# SmartEVSEv2_2.net
KiCad netlist of a schematic drawn in EAGLE
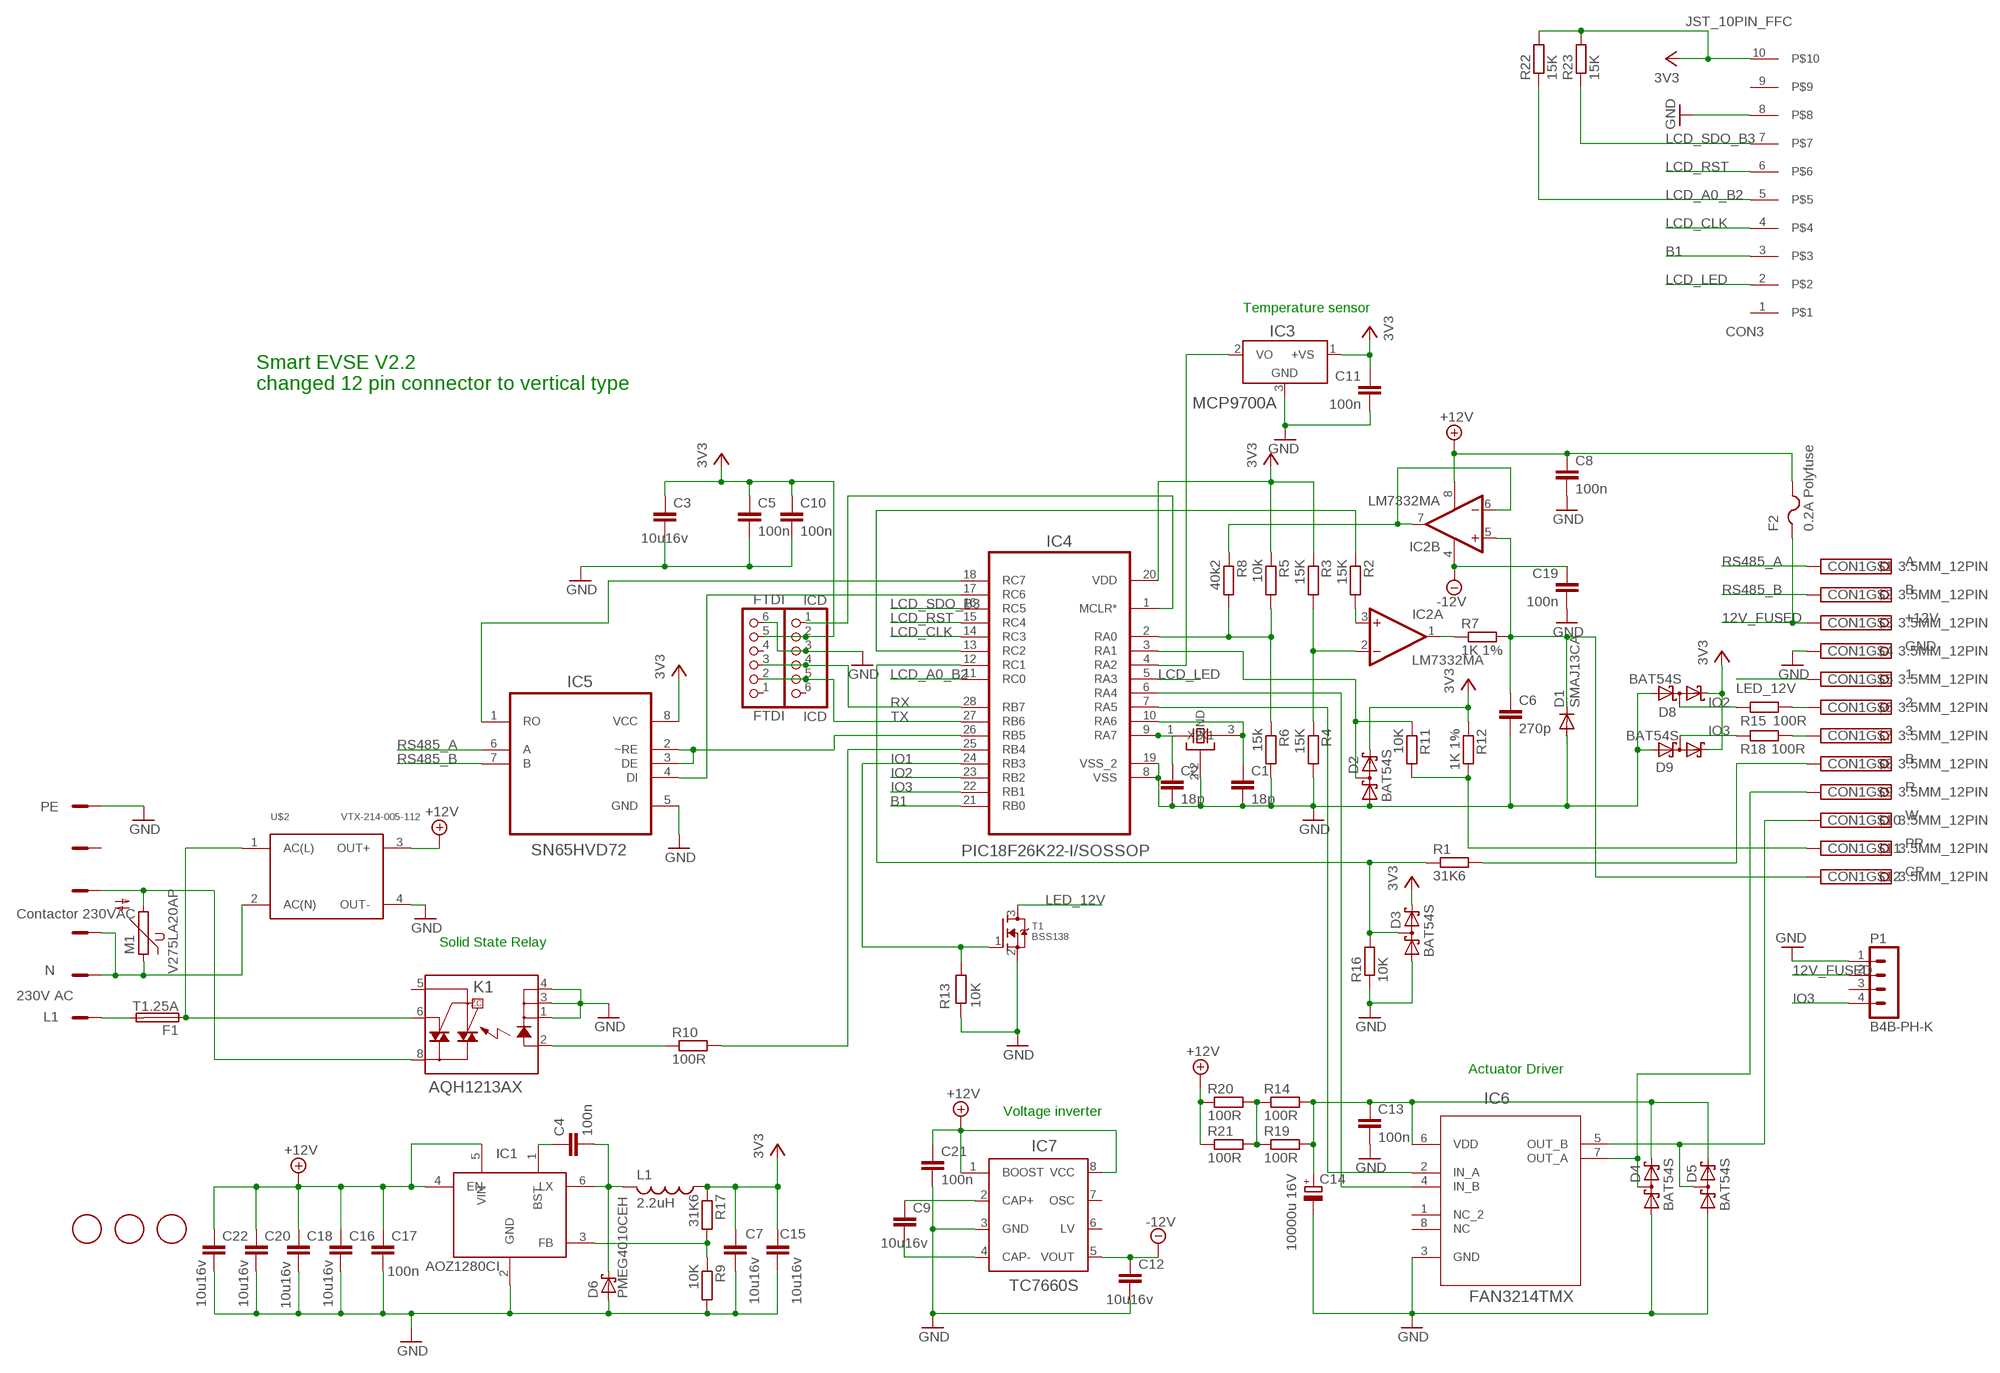
[diagram p0: schematic, sheet 1]

(export (version "E")
  (design (tool "Eeschema 10.0.6"))
  (components
    (comp (ref "C1")
      (value "18p")
      (footprint "eagle-import:C0603")
      (libsource (lib "eagle-import") (part "C-EUC0603"))
    )
    (comp (ref "C2")
      (value "18p")
      (footprint "eagle-import:C0603")
      (libsource (lib "eagle-import") (part "C-EUC0603"))
    )
    (comp (ref "C3")
      (value "10u16v")
      (footprint "eagle-import:C0805")
      (libsource (lib "eagle-import") (part "C-EUC0805"))
    )
    (comp (ref "C4")
      (value "100n")
      (footprint "eagle-import:C0603")
      (libsource (lib "eagle-import") (part "C-EUC0603"))
    )
    (comp (ref "C5")
      (value "100n")
      (footprint "eagle-import:C0603")
      (libsource (lib "eagle-import") (part "C-EUC0603"))
    )
    (comp (ref "C6")
      (value "270p")
      (footprint "eagle-import:C0805")
      (libsource (lib "eagle-import") (part "C-EUC0805"))
    )
    (comp (ref "C7")
      (value "10u16v")
      (footprint "eagle-import:C0805")
      (libsource (lib "eagle-import") (part "C-EUC0805"))
    )
    (comp (ref "C8")
      (value "100n")
      (footprint "eagle-import:C0603")
      (libsource (lib "eagle-import") (part "C-EUC0603"))
    )
    (comp (ref "C9")
      (value "10u16v")
      (footprint "eagle-import:C0805")
      (libsource (lib "eagle-import") (part "C-EUC0805"))
    )
    (comp (ref "C10")
      (value "100n")
      (footprint "eagle-import:C0603")
      (libsource (lib "eagle-import") (part "C-EUC0603"))
    )
    (comp (ref "C11")
      (value "100n")
      (footprint "eagle-import:C0603")
      (libsource (lib "eagle-import") (part "C-EUC0603"))
    )
    (comp (ref "C12")
      (value "10u16v")
      (footprint "eagle-import:C0805")
      (libsource (lib "eagle-import") (part "C-EUC0805"))
    )
    (comp (ref "C13")
      (value "100n")
      (footprint "eagle-import:C0603")
      (libsource (lib "eagle-import") (part "C-EUC0603"))
    )
    (comp (ref "C14")
      (value "10000u 16V")
      (footprint "eagle-import:EB22,5D")
      (libsource (lib "eagle-import") (part "CPOL-EUE10-22.5"))
    )
    (comp (ref "C15")
      (value "10u16v")
      (footprint "eagle-import:C0805")
      (libsource (lib "eagle-import") (part "C-EUC0805"))
    )
    (comp (ref "C16")
      (value "10u16v")
      (footprint "eagle-import:C0805")
      (libsource (lib "eagle-import") (part "C-EUC0805"))
    )
    (comp (ref "C17")
      (value "100n")
      (footprint "eagle-import:C0603")
      (libsource (lib "eagle-import") (part "C-EUC0603"))
    )
    (comp (ref "C18")
      (value "10u16v")
      (footprint "eagle-import:C0805")
      (libsource (lib "eagle-import") (part "C-EUC0805"))
    )
    (comp (ref "C19")
      (value "100n")
      (footprint "eagle-import:C0603")
      (libsource (lib "eagle-import") (part "C-EUC0603"))
    )
    (comp (ref "C20")
      (value "10u16v")
      (footprint "eagle-import:C0805")
      (libsource (lib "eagle-import") (part "C-EUC0805"))
    )
    (comp (ref "C21")
      (value "100n")
      (footprint "eagle-import:C0603")
      (libsource (lib "eagle-import") (part "C-EUC0603"))
    )
    (comp (ref "C22")
      (value "10u16v")
      (footprint "eagle-import:C0805")
      (libsource (lib "eagle-import") (part "C-EUC0805"))
    )
    (comp (ref "CON1")
      (value "3.5MM_12PIN")
      (footprint "eagle-import:12PIN")
      (libsource (lib "eagle-import") (part "3.5MM_12PIN"))
    )
    (comp (ref "CON2")
      (value "DG128-7.5")
      (footprint "eagle-import:P_AST027-06")
      (libsource (lib "eagle-import") (part "AST027-06"))
    )
    (comp (ref "CON3")
      (value "JST_10PIN_FFC")
      (footprint "eagle-import:JST_10PIN_FFC")
      (libsource (lib "eagle-import") (part "JST_10PIN_FFC"))
    )
    (comp (ref "D1")
      (value "SMAJ13CA")
      (footprint "eagle-import:DO214AC")
      (libsource (lib "eagle-import") (part "DIODE-DO214AC"))
    )
    (comp (ref "D2")
      (value "BAT54S")
      (footprint "eagle-import:SOT23")
      (libsource (lib "eagle-import") (part "BAT54S"))
    )
    (comp (ref "D3")
      (value "BAT54S")
      (footprint "eagle-import:SOT23")
      (libsource (lib "eagle-import") (part "BAT54S"))
    )
    (comp (ref "D4")
      (value "BAT54S")
      (footprint "eagle-import:SOT23")
      (libsource (lib "eagle-import") (part "BAT54S"))
    )
    (comp (ref "D5")
      (value "BAT54S")
      (footprint "eagle-import:SOT23")
      (libsource (lib "eagle-import") (part "BAT54S"))
    )
    (comp (ref "D6")
      (value "PMEG4010CEH")
      (footprint "eagle-import:SOD-123FL")
      (libsource (lib "eagle-import") (part "PMEG4010CEH"))
    )
    (comp (ref "D8")
      (value "BAT54S")
      (footprint "eagle-import:SOT23")
      (libsource (lib "eagle-import") (part "BAT54S"))
    )
    (comp (ref "D9")
      (value "BAT54S")
      (footprint "eagle-import:SOT23")
      (libsource (lib "eagle-import") (part "BAT54S"))
    )
    (comp (ref "F1")
      (value "T1.25A")
      (footprint "eagle-import:TE5")
      (libsource (lib "eagle-import") (part "FUSETE5"))
    )
    (comp (ref "F2")
      (value "0.2A Polyfuse")
      (footprint "eagle-import:R1210")
      (libsource (lib "eagle-import") (part "PTCFUSE-1210"))
    )
    (comp (ref "FTDI")
      (value "FTDI")
      (footprint "eagle-import:1X06-BIGLOCK")
      (libsource (lib "eagle-import") (part "PINHD-1X6LOCK"))
    )
    (comp (ref "IC1")
      (value "AOZ1280CI")
      (footprint "eagle-import:SOT23-6")
      (libsource (lib "eagle-import") (part "AOZ1280CISOT23"))
    )
    (comp (ref "IC2")
      (value "LM7332MA")
      (footprint "eagle-import:SO08")
      (libsource (lib "eagle-import") (part "1458DLM"))
    )
    (comp (ref "IC3")
      (value "MCP9700A")
      (footprint "eagle-import:SOT23")
      (libsource (lib "eagle-import") (part "LM50"))
    )
    (comp (ref "IC4")
      (value "PIC18F26K22-I/SOSSOP")
      (footprint "eagle-import:SOP65P780X200-28N")
      (libsource (lib "eagle-import") (part "PIC18F25K22-I/SOSSOP"))
    )
    (comp (ref "IC5")
      (value "SN65HVD72")
      (footprint "eagle-import:SOIC127P600X175-8N")
      (fields (field (name "MPN") "MAX487ECSA+"))
      (libsource (lib "eagle-import") (part "MAX487ECSA+"))
    )
    (comp (ref "IC6")
      (value "FAN3214TMX")
      (footprint "eagle-import:SOIC127P600X175-8N")
      (fields (field (name "MPN") "TC4424AVOA"))
      (libsource (lib "eagle-import") (part "TC4424AVOA"))
    )
    (comp (ref "IC7")
      (value "TC7660S")
      (footprint "eagle-import:SO08")
      (libsource (lib "eagle-import") (part "TL7660"))
    )
    (comp (ref "ICD")
      (value "ICD")
      (footprint "eagle-import:1X06")
      (libsource (lib "eagle-import") (part "pinhead_PINHD-1X6"))
    )
    (comp (ref "K1")
      (value "AQH1213AX")
      (footprint "eagle-import:DIL07SMD")
      (libsource (lib "eagle-import") (part "AQH213A"))
    )
    (comp (ref "L1")
      (value "2.2uH")
      (footprint "eagle-import:MCSD43")
      (libsource (lib "eagle-import") (part "MCSD43"))
    )
    (comp (ref "M1")
      (value "V275LA20AP")
      (footprint "eagle-import:S14K40")
      (libsource (lib "eagle-import") (part "S14K40"))
    )
    (comp (ref "P1")
      (value "B4B-PH-K")
      (footprint "eagle-import:B4B-PH-K")
      (libsource (lib "eagle-import") (part "B4B-PH-K"))
    )
    (comp (ref "Q1")
      (value "CTS_32X25_SMD")
      (footprint "eagle-import:CTS_32X25")
      (libsource (lib "eagle-import") (part "CTS_32X25_SMD"))
    )
    (comp (ref "R1")
      (value "31K6")
      (footprint "eagle-import:R0603")
      (libsource (lib "eagle-import") (part "R-EU_R0603"))
    )
    (comp (ref "R2")
      (value "15K")
      (footprint "eagle-import:R0603")
      (libsource (lib "eagle-import") (part "R-EU_R0603"))
    )
    (comp (ref "R3")
      (value "15K")
      (footprint "eagle-import:R0603")
      (libsource (lib "eagle-import") (part "R-EU_R0603"))
    )
    (comp (ref "R4")
      (value "15K")
      (footprint "eagle-import:R0603")
      (libsource (lib "eagle-import") (part "R-EU_R0603"))
    )
    (comp (ref "R5")
      (value "10k")
      (footprint "eagle-import:R0603")
      (libsource (lib "eagle-import") (part "R-EU_R0603"))
    )
    (comp (ref "R6")
      (value "15k")
      (footprint "eagle-import:R0603")
      (libsource (lib "eagle-import") (part "R-EU_R0603"))
    )
    (comp (ref "R7")
      (value "1K 1%")
      (footprint "eagle-import:R0603")
      (libsource (lib "eagle-import") (part "R-EU_R0603"))
    )
    (comp (ref "R8")
      (value "40k2")
      (footprint "eagle-import:R0603")
      (libsource (lib "eagle-import") (part "R-EU_R0603"))
    )
    (comp (ref "R9")
      (value "10K")
      (footprint "eagle-import:R0603")
      (libsource (lib "eagle-import") (part "R-EU_R0603"))
    )
    (comp (ref "R10")
      (value "100R")
      (footprint "eagle-import:R0603")
      (libsource (lib "eagle-import") (part "R-EU_R0603"))
    )
    (comp (ref "R11")
      (value "10K")
      (footprint "eagle-import:R0603")
      (libsource (lib "eagle-import") (part "R-EU_R0603"))
    )
    (comp (ref "R12")
      (value "1K 1%")
      (footprint "eagle-import:R0603")
      (libsource (lib "eagle-import") (part "R-EU_R0603"))
    )
    (comp (ref "R13")
      (value "10K")
      (footprint "eagle-import:R0603")
      (libsource (lib "eagle-import") (part "R-EU_R0603"))
    )
    (comp (ref "R14")
      (value "100R")
      (footprint "eagle-import:R0603")
      (libsource (lib "eagle-import") (part "R-EU_R0603"))
    )
    (comp (ref "R15")
      (value "100R")
      (footprint "eagle-import:R0603")
      (libsource (lib "eagle-import") (part "R-EU_R0603"))
    )
    (comp (ref "R16")
      (value "10K")
      (footprint "eagle-import:R0603")
      (libsource (lib "eagle-import") (part "R-EU_R0603"))
    )
    (comp (ref "R17")
      (value "31K6")
      (footprint "eagle-import:R0603")
      (libsource (lib "eagle-import") (part "R-EU_R0603"))
    )
    (comp (ref "R18")
      (value "100R")
      (footprint "eagle-import:R0603")
      (libsource (lib "eagle-import") (part "R-EU_R0603"))
    )
    (comp (ref "R19")
      (value "100R")
      (footprint "eagle-import:R0603")
      (libsource (lib "eagle-import") (part "R-EU_R0603"))
    )
    (comp (ref "R20")
      (value "100R")
      (footprint "eagle-import:R0603")
      (libsource (lib "eagle-import") (part "R-EU_R0603"))
    )
    (comp (ref "R21")
      (value "100R")
      (footprint "eagle-import:R0603")
      (libsource (lib "eagle-import") (part "R-EU_R0603"))
    )
    (comp (ref "R22")
      (value "15K")
      (footprint "eagle-import:R0603")
      (libsource (lib "eagle-import") (part "R-EU_R0603"))
    )
    (comp (ref "R23")
      (value "15K")
      (footprint "eagle-import:R0603")
      (libsource (lib "eagle-import") (part "R-EU_R0603"))
    )
    (comp (ref "T1")
      (value "BSS138")
      (footprint "eagle-import:SOT23")
      (libsource (lib "eagle-import") (part "MOSFET-NREFLOW"))
    )
    (comp (ref "U$1")
      (value "FIDUCIAL")
      (footprint "eagle-import:FIDUCIAL_1MM")
      (libsource (lib "eagle-import") (part "FIDUCIAL"))
    )
    (comp (ref "U$2")
      (value "VTX-214-005-112")
      (footprint "eagle-import:VTX-214-005-112")
      (libsource (lib "eagle-import") (part "VTX-214-005-112"))
    )
    (comp (ref "U$3")
      (value "FIDUCIAL")
      (footprint "eagle-import:FIDUCIAL_1MM")
      (libsource (lib "eagle-import") (part "FIDUCIAL"))
    )
    (comp (ref "U$4")
      (value "FIDUCIAL")
      (footprint "eagle-import:FIDUCIAL_1MM")
      (libsource (lib "eagle-import") (part "FIDUCIAL"))
    )
  )
  (nets
    (net (code "1") (name "+12V") (class "Default")
      (node (ref "C16") (pin "1") (pinfunction "1_1") (pintype "passive"))
      (node (ref "C17") (pin "1") (pinfunction "1_1") (pintype "passive"))
      (node (ref "C18") (pin "1") (pinfunction "1_1") (pintype "passive"))
      (node (ref "C20") (pin "1") (pinfunction "1_1") (pintype "passive"))
      (node (ref "C21") (pin "1") (pinfunction "1_1") (pintype "passive"))
      (node (ref "C22") (pin "1") (pinfunction "1_1") (pintype "passive"))
      (node (ref "C8") (pin "1") (pinfunction "1_1") (pintype "passive"))
      (node (ref "F2") (pin "2") (pinfunction "2_2") (pintype "passive"))
      (node (ref "IC1") (pin "4") (pinfunction "EN_4") (pintype "bidirectional"))
      (node (ref "IC1") (pin "5") (pinfunction "VIN_5") (pintype "bidirectional"))
      (node (ref "IC2") (pin "8") (pinfunction "V+_8") (pintype "power_in"))
      (node (ref "IC7") (pin "1") (pinfunction "BOOST_1") (pintype "bidirectional"))
      (node (ref "IC7") (pin "8") (pinfunction "VCC_8") (pintype "power_in"))
      (node (ref "R20") (pin "1") (pinfunction "1_1") (pintype "passive"))
      (node (ref "R21") (pin "1") (pinfunction "1_1") (pintype "passive"))
      (node (ref "U$2") (pin "3") (pinfunction "OUT+_3") (pintype "passive"))
    )
    (net (code "2") (name "-12V") (class "Default")
      (node (ref "C12") (pin "1") (pinfunction "1_1") (pintype "passive"))
      (node (ref "C19") (pin "1") (pinfunction "1_1") (pintype "passive"))
      (node (ref "IC2") (pin "4") (pinfunction "V-_4") (pintype "power_in"))
      (node (ref "IC7") (pin "5") (pinfunction "VOUT_5") (pintype "passive"))
    )
    (net (code "3") (name "/12V_FUSED") (class "Default")
      (node (ref "CON1") (pin "3") (pinfunction "K_3") (pintype "passive"))
      (node (ref "F2") (pin "1") (pinfunction "1_1") (pintype "passive"))
      (node (ref "P1") (pin "2") (pinfunction "2_2") (pintype "passive"))
    )
    (net (code "4") (name "/B1") (class "Default")
      (node (ref "CON3") (pin "3") (pinfunction "P$3_3") (pintype "bidirectional"))
      (node (ref "IC4") (pin "21") (pinfunction "RB0_21") (pintype "bidirectional"))
    )
    (net (code "5") (name "/IO1") (class "Default")
      (node (ref "IC4") (pin "24") (pinfunction "RB3_24") (pintype "bidirectional"))
      (node (ref "R13") (pin "2") (pinfunction "2_2") (pintype "passive"))
      (node (ref "T1") (pin "1") (pinfunction "G_1") (pintype "bidirectional"))
    )
    (net (code "6") (name "/IO2") (class "Default")
      (node (ref "D8") (pin "3") (pinfunction "C1A2_3") (pintype "passive"))
      (node (ref "IC4") (pin "23") (pinfunction "RB2_23") (pintype "bidirectional"))
      (node (ref "R15") (pin "1") (pinfunction "1_1") (pintype "passive"))
    )
    (net (code "7") (name "/IO3") (class "Default")
      (node (ref "D9") (pin "3") (pinfunction "C1A2_3") (pintype "passive"))
      (node (ref "IC4") (pin "22") (pinfunction "RB1_22") (pintype "bidirectional"))
      (node (ref "P1") (pin "4") (pinfunction "4_4") (pintype "passive"))
      (node (ref "R18") (pin "1") (pinfunction "1_1") (pintype "passive"))
    )
    (net (code "8") (name "/LCD_A0_B2") (class "Default")
      (node (ref "CON3") (pin "5") (pinfunction "P$5_5") (pintype "bidirectional"))
      (node (ref "IC4") (pin "11") (pinfunction "RC0_11") (pintype "bidirectional"))
      (node (ref "R22") (pin "1") (pinfunction "1_1") (pintype "passive"))
    )
    (net (code "9") (name "/LCD_CLK") (class "Default")
      (node (ref "CON3") (pin "4") (pinfunction "P$4_4") (pintype "bidirectional"))
      (node (ref "IC4") (pin "14") (pinfunction "RC3_14") (pintype "bidirectional"))
    )
    (net (code "10") (name "/LCD_LED") (class "Default")
      (node (ref "CON3") (pin "2") (pinfunction "P$2_2") (pintype "bidirectional"))
      (node (ref "IC4") (pin "5") (pinfunction "RA3_5") (pintype "bidirectional"))
    )
    (net (code "11") (name "/LCD_RST") (class "Default")
      (node (ref "CON3") (pin "6") (pinfunction "P$6_6") (pintype "bidirectional"))
      (node (ref "IC4") (pin "15") (pinfunction "RC4_15") (pintype "bidirectional"))
    )
    (net (code "12") (name "/LCD_SDO_B3") (class "Default")
      (node (ref "CON3") (pin "7") (pinfunction "P$7_7") (pintype "bidirectional"))
      (node (ref "IC4") (pin "16") (pinfunction "RC5_16") (pintype "bidirectional"))
      (node (ref "R23") (pin "1") (pinfunction "1_1") (pintype "passive"))
    )
    (net (code "13") (name "/LED_12V") (class "Default")
      (node (ref "CON1") (pin "5") (pinfunction "K_5") (pintype "passive"))
      (node (ref "T1") (pin "3") (pinfunction "D_3") (pintype "bidirectional"))
    )
    (net (code "14") (name "/RS485_A") (class "Default")
      (node (ref "CON1") (pin "1") (pinfunction "K_1") (pintype "passive"))
      (node (ref "IC5") (pin "6") (pinfunction "A_6") (pintype "bidirectional"))
    )
    (net (code "15") (name "/RS485_B") (class "Default")
      (node (ref "CON1") (pin "2") (pinfunction "K_2") (pintype "passive"))
      (node (ref "IC5") (pin "7") (pinfunction "B_7") (pintype "bidirectional"))
    )
    (net (code "16") (name "/RX") (class "Default")
      (node (ref "FTDI") (pin "3") (pinfunction "3_3") (pintype "passive"))
      (node (ref "IC4") (pin "28") (pinfunction "RB7_28") (pintype "bidirectional"))
      (node (ref "ICD") (pin "4") (pinfunction "4_4") (pintype "passive"))
    )
    (net (code "17") (name "/TX") (class "Default")
      (node (ref "FTDI") (pin "2") (pinfunction "2_2") (pintype "passive"))
      (node (ref "IC4") (pin "27") (pinfunction "RB6_27") (pintype "bidirectional"))
      (node (ref "ICD") (pin "5") (pinfunction "5_5") (pintype "passive"))
    )
    (net (code "18") (name "3V3") (class "Default")
      (node (ref "C10") (pin "1") (pinfunction "1_1") (pintype "passive"))
      (node (ref "C11") (pin "1") (pinfunction "1_1") (pintype "passive"))
      (node (ref "C15") (pin "2") (pinfunction "2_2") (pintype "passive"))
      (node (ref "C3") (pin "1") (pinfunction "1_1") (pintype "passive"))
      (node (ref "C5") (pin "1") (pinfunction "1_1") (pintype "passive"))
      (node (ref "C7") (pin "2") (pinfunction "2_2") (pintype "passive"))
      (node (ref "CON3") (pin "10") (pinfunction "P$10_10") (pintype "bidirectional"))
      (node (ref "D2") (pin "2") (pinfunction "C2_2") (pintype "passive"))
      (node (ref "D3") (pin "2") (pinfunction "C2_2") (pintype "passive"))
      (node (ref "D8") (pin "2") (pinfunction "C2_2") (pintype "passive"))
      (node (ref "D9") (pin "2") (pinfunction "C2_2") (pintype "passive"))
      (node (ref "FTDI") (pin "5") (pinfunction "5_5") (pintype "passive"))
      (node (ref "IC3") (pin "1") (pinfunction "+VS_1") (pintype "input"))
      (node (ref "IC4") (pin "20") (pinfunction "VDD_20") (pintype "power_in"))
      (node (ref "IC5") (pin "8") (pinfunction "VCC_8") (pintype "power_in"))
      (node (ref "ICD") (pin "2") (pinfunction "2_2") (pintype "passive"))
      (node (ref "L1") (pin "1") (pinfunction "1_1") (pintype "passive"))
      (node (ref "R12") (pin "1") (pinfunction "1_1") (pintype "passive"))
      (node (ref "R17") (pin "1") (pinfunction "1_1") (pintype "passive"))
      (node (ref "R22") (pin "2") (pinfunction "2_2") (pintype "passive"))
      (node (ref "R23") (pin "2") (pinfunction "2_2") (pintype "passive"))
      (node (ref "R3") (pin "1") (pinfunction "1_1") (pintype "passive"))
      (node (ref "R5") (pin "1") (pinfunction "1_1") (pintype "passive"))
    )
    (net (code "19") (name "GND") (class "Default")
      (node (ref "C1") (pin "2") (pinfunction "2_2") (pintype "passive"))
      (node (ref "C10") (pin "2") (pinfunction "2_2") (pintype "passive"))
      (node (ref "C11") (pin "2") (pinfunction "2_2") (pintype "passive"))
      (node (ref "C12") (pin "2") (pinfunction "2_2") (pintype "passive"))
      (node (ref "C13") (pin "2") (pinfunction "2_2") (pintype "passive"))
      (node (ref "C14") (pin "-") (pinfunction "-_-") (pintype "passive"))
      (node (ref "C15") (pin "1") (pinfunction "1_1") (pintype "passive"))
      (node (ref "C16") (pin "2") (pinfunction "2_2") (pintype "passive"))
      (node (ref "C17") (pin "2") (pinfunction "2_2") (pintype "passive"))
      (node (ref "C18") (pin "2") (pinfunction "2_2") (pintype "passive"))
      (node (ref "C19") (pin "2") (pinfunction "2_2") (pintype "passive"))
      (node (ref "C2") (pin "2") (pinfunction "2_2") (pintype "passive"))
      (node (ref "C20") (pin "2") (pinfunction "2_2") (pintype "passive"))
      (node (ref "C21") (pin "2") (pinfunction "2_2") (pintype "passive"))
      (node (ref "C22") (pin "2") (pinfunction "2_2") (pintype "passive"))
      (node (ref "C3") (pin "2") (pinfunction "2_2") (pintype "passive"))
      (node (ref "C5") (pin "2") (pinfunction "2_2") (pintype "passive"))
      (node (ref "C6") (pin "2") (pinfunction "2_2") (pintype "passive"))
      (node (ref "C7") (pin "1") (pinfunction "1_1") (pintype "passive"))
      (node (ref "C8") (pin "2") (pinfunction "2_2") (pintype "passive"))
      (node (ref "CON1") (pin "4") (pinfunction "K_4") (pintype "passive"))
      (node (ref "CON2") (pin "P$6") (pinfunction "SK_P$6") (pintype "passive"))
      (node (ref "CON3") (pin "8") (pinfunction "P$8_8") (pintype "bidirectional"))
      (node (ref "D1") (pin "A") (pinfunction "A_A") (pintype "passive"))
      (node (ref "D2") (pin "1") (pinfunction "A1_1") (pintype "passive"))
      (node (ref "D3") (pin "1") (pinfunction "A1_1") (pintype "passive"))
      (node (ref "D4") (pin "1") (pinfunction "A1_1") (pintype "passive"))
      (node (ref "D5") (pin "1") (pinfunction "A1_1") (pintype "passive"))
      (node (ref "D6") (pin "A") (pinfunction "A_A") (pintype "passive"))
      (node (ref "D8") (pin "1") (pinfunction "A1_1") (pintype "passive"))
      (node (ref "D9") (pin "1") (pinfunction "A1_1") (pintype "passive"))
      (node (ref "FTDI") (pin "6") (pinfunction "6_6") (pintype "passive"))
      (node (ref "IC1") (pin "2") (pinfunction "GND_2") (pintype "bidirectional"))
      (node (ref "IC3") (pin "3") (pinfunction "GND_3") (pintype "power_in"))
      (node (ref "IC4") (pin "19") (pinfunction "VSS_2_19") (pintype "power_in"))
      (node (ref "IC4") (pin "8") (pinfunction "VSS_8") (pintype "power_in"))
      (node (ref "IC5") (pin "5") (pinfunction "GND_5") (pintype "passive"))
      (node (ref "IC6") (pin "3") (pinfunction "GND_3") (pintype "passive"))
      (node (ref "IC7") (pin "3") (pinfunction "GND_3") (pintype "power_in"))
      (node (ref "ICD") (pin "3") (pinfunction "3_3") (pintype "passive"))
      (node (ref "K1") (pin "1") (pinfunction "K_1") (pintype "passive"))
      (node (ref "K1") (pin "3") (pinfunction "K1_3") (pintype "passive"))
      (node (ref "K1") (pin "4") (pinfunction "K2_4") (pintype "passive"))
      (node (ref "P1") (pin "1") (pinfunction "1_1") (pintype "passive"))
      (node (ref "Q1") (pin "2") (pinfunction "GND_2") (pintype "power_in"))
      (node (ref "Q1") (pin "4") (pinfunction "GND_4") (pintype "power_in"))
      (node (ref "R13") (pin "1") (pinfunction "1_1") (pintype "passive"))
      (node (ref "R16") (pin "1") (pinfunction "1_1") (pintype "passive"))
      (node (ref "R4") (pin "2") (pinfunction "2_2") (pintype "passive"))
      (node (ref "R6") (pin "2") (pinfunction "2_2") (pintype "passive"))
      (node (ref "R9") (pin "2") (pinfunction "2_2") (pintype "passive"))
      (node (ref "T1") (pin "2") (pinfunction "S_2") (pintype "bidirectional"))
      (node (ref "U$2") (pin "4") (pinfunction "OUT-_4") (pintype "passive"))
    )
    (net (code "20") (name "Net-(CON1B-K)") (class "Default")
      (node (ref "CON1") (pin "10") (pinfunction "K_10") (pintype "passive"))
      (node (ref "D5") (pin "3") (pinfunction "C1A2_3") (pintype "passive"))
      (node (ref "IC6") (pin "5") (pinfunction "OUT_B_5") (pintype "output"))
    )
    (net (code "21") (name "Net-(CON1C-K)") (class "Default")
      (node (ref "CON1") (pin "11") (pinfunction "K_11") (pintype "passive"))
      (node (ref "R11") (pin "2") (pinfunction "2_2") (pintype "passive"))
      (node (ref "R12") (pin "2") (pinfunction "2_2") (pintype "passive"))
    )
    (net (code "22") (name "Net-(CON1D-K)") (class "Default")
      (node (ref "C6") (pin "1") (pinfunction "1_1") (pintype "passive"))
      (node (ref "CON1") (pin "12") (pinfunction "K_12") (pintype "passive"))
      (node (ref "D1") (pin "C") (pinfunction "C_C") (pintype "passive"))
      (node (ref "IC2") (pin "5") (pinfunction "+IN_5") (pintype "input"))
      (node (ref "R7") (pin "2") (pinfunction "2_2") (pintype "passive"))
    )
    (net (code "23") (name "Net-(CON1I-K)") (class "Default")
      (node (ref "CON1") (pin "6") (pinfunction "K_6") (pintype "passive"))
      (node (ref "R15") (pin "2") (pinfunction "2_2") (pintype "passive"))
    )
    (net (code "24") (name "Net-(CON1J-K)") (class "Default")
      (node (ref "CON1") (pin "7") (pinfunction "K_7") (pintype "passive"))
      (node (ref "R18") (pin "2") (pinfunction "2_2") (pintype "passive"))
    )
    (net (code "25") (name "Net-(CON1K-K)") (class "Default")
      (node (ref "CON1") (pin "8") (pinfunction "K_8") (pintype "passive"))
      (node (ref "R1") (pin "2") (pinfunction "2_2") (pintype "passive"))
    )
    (net (code "26") (name "Net-(CON1L-K)") (class "Default")
      (node (ref "CON1") (pin "9") (pinfunction "K_9") (pintype "passive"))
      (node (ref "D4") (pin "3") (pinfunction "C1A2_3") (pintype "passive"))
      (node (ref "IC6") (pin "7") (pinfunction "OUT_A_7") (pintype "output"))
    )
    (net (code "27") (name "Net-(CON2A-SK)") (class "Default")
      (node (ref "CON2") (pin "P$1") (pinfunction "SK_P$1") (pintype "passive"))
      (node (ref "F1") (pin "2") (pinfunction "2_2") (pintype "passive"))
    )
    (net (code "28") (name "Net-(CON2B-SK)") (class "Default")
      (node (ref "CON2") (pin "P$2") (pinfunction "SK_P$2") (pintype "passive"))
      (node (ref "CON2") (pin "P$3") (pinfunction "SK_P$3") (pintype "passive"))
      (node (ref "M1") (pin "1") (pinfunction "1_1") (pintype "passive"))
      (node (ref "U$2") (pin "2") (pinfunction "AC(N)_2") (pintype "input"))
    )
    (net (code "29") (name "Net-(CON2D-SK)") (class "Default")
      (node (ref "CON2") (pin "P$4") (pinfunction "SK_P$4") (pintype "passive"))
      (node (ref "K1") (pin "8") (pinfunction "DS1_8") (pintype "passive"))
      (node (ref "M1") (pin "2") (pinfunction "2_2") (pintype "passive"))
    )
    (net (code "30") (name "Net-(D2-C1A2)") (class "Default")
      (node (ref "D2") (pin "3") (pinfunction "C1A2_3") (pintype "passive"))
      (node (ref "IC4") (pin "3") (pinfunction "RA1_3") (pintype "bidirectional"))
      (node (ref "R11") (pin "1") (pinfunction "1_1") (pintype "passive"))
    )
    (net (code "31") (name "Net-(D3-C1A2)") (class "Default")
      (node (ref "D3") (pin "3") (pinfunction "C1A2_3") (pintype "passive"))
      (node (ref "IC4") (pin "12") (pinfunction "RC1_12") (pintype "bidirectional"))
      (node (ref "R1") (pin "1") (pinfunction "1_1") (pintype "passive"))
      (node (ref "R16") (pin "2") (pinfunction "2_2") (pintype "passive"))
    )
    (net (code "32") (name "Net-(D4-C2)") (class "Default")
      (node (ref "C13") (pin "1") (pinfunction "1_1") (pintype "passive"))
      (node (ref "C14") (pin "+") (pinfunction "+_+") (pintype "passive"))
      (node (ref "D4") (pin "2") (pinfunction "C2_2") (pintype "passive"))
      (node (ref "D5") (pin "2") (pinfunction "C2_2") (pintype "passive"))
      (node (ref "IC6") (pin "6") (pinfunction "VDD_6") (pintype "power_in"))
      (node (ref "R14") (pin "2") (pinfunction "2_2") (pintype "passive"))
      (node (ref "R19") (pin "2") (pinfunction "2_2") (pintype "passive"))
    )
    (net (code "33") (name "Net-(IC1-BST)") (class "Default")
      (node (ref "C4") (pin "1") (pinfunction "1_1") (pintype "passive"))
      (node (ref "IC1") (pin "1") (pinfunction "BST_1") (pintype "bidirectional"))
    )
    (net (code "34") (name "Net-(IC1-FB)") (class "Default")
      (node (ref "IC1") (pin "3") (pinfunction "FB_3") (pintype "bidirectional"))
      (node (ref "R17") (pin "2") (pinfunction "2_2") (pintype "passive"))
      (node (ref "R9") (pin "1") (pinfunction "1_1") (pintype "passive"))
    )
    (net (code "35") (name "Net-(IC1-LX)") (class "Default")
      (node (ref "C4") (pin "2") (pinfunction "2_2") (pintype "passive"))
      (node (ref "D6") (pin "C") (pinfunction "C_C") (pintype "passive"))
      (node (ref "IC1") (pin "6") (pinfunction "LX_6") (pintype "bidirectional"))
      (node (ref "L1") (pin "2") (pinfunction "2_2") (pintype "passive"))
    )
    (net (code "36") (name "Net-(IC2A-+IN)") (class "Default")
      (node (ref "IC2") (pin "3") (pinfunction "+IN_3") (pintype "input"))
      (node (ref "R2") (pin "2") (pinfunction "2_2") (pintype "passive"))
    )
    (net (code "37") (name "Net-(IC2A--IN)") (class "Default")
      (node (ref "IC2") (pin "2") (pinfunction "-IN_2") (pintype "input"))
      (node (ref "R3") (pin "2") (pinfunction "2_2") (pintype "passive"))
      (node (ref "R4") (pin "1") (pinfunction "1_1") (pintype "passive"))
    )
    (net (code "38") (name "Net-(IC2A-OUT)") (class "Default")
      (node (ref "IC2") (pin "1") (pinfunction "OUT_1") (pintype "output"))
      (node (ref "R7") (pin "1") (pinfunction "1_1") (pintype "passive"))
    )
    (net (code "39") (name "Net-(IC2B--IN)") (class "Default")
      (node (ref "IC2") (pin "6") (pinfunction "-IN_6") (pintype "input"))
      (node (ref "IC2") (pin "7") (pinfunction "OUT_7") (pintype "output"))
      (node (ref "R8") (pin "1") (pinfunction "1_1") (pintype "passive"))
    )
    (net (code "40") (name "Net-(IC3-VO)") (class "Default")
      (node (ref "IC3") (pin "2") (pinfunction "VO_2") (pintype "input"))
      (node (ref "IC4") (pin "4") (pinfunction "RA2_4") (pintype "bidirectional"))
    )
    (net (code "41") (name "Net-(IC4-MCLR*)") (class "Default")
      (node (ref "IC4") (pin "1") (pinfunction "MCLR*_1") (pintype "input"))
      (node (ref "ICD") (pin "1") (pinfunction "1_1") (pintype "passive"))
    )
    (net (code "42") (name "Net-(IC4-RA0)") (class "Default")
      (node (ref "IC4") (pin "2") (pinfunction "RA0_2") (pintype "bidirectional"))
      (node (ref "R5") (pin "2") (pinfunction "2_2") (pintype "passive"))
      (node (ref "R6") (pin "1") (pinfunction "1_1") (pintype "passive"))
      (node (ref "R8") (pin "2") (pinfunction "2_2") (pintype "passive"))
    )
    (net (code "43") (name "Net-(IC4-RA4)") (class "Default")
      (node (ref "IC4") (pin "6") (pinfunction "RA4_6") (pintype "bidirectional"))
      (node (ref "IC6") (pin "4") (pinfunction "IN_B_4") (pintype "input"))
    )
    (net (code "44") (name "Net-(IC4-RA5)") (class "Default")
      (node (ref "IC4") (pin "7") (pinfunction "RA5_7") (pintype "bidirectional"))
      (node (ref "IC6") (pin "2") (pinfunction "IN_A_2") (pintype "input"))
    )
    (net (code "45") (name "Net-(IC4-RA6)") (class "Default")
      (node (ref "C1") (pin "1") (pinfunction "1_1") (pintype "passive"))
      (node (ref "IC4") (pin "10") (pinfunction "RA6_10") (pintype "bidirectional"))
      (node (ref "Q1") (pin "3") (pinfunction "X2_3") (pintype "bidirectional"))
    )
    (net (code "46") (name "Net-(IC4-RA7)") (class "Default")
      (node (ref "C2") (pin "1") (pinfunction "1_1") (pintype "passive"))
      (node (ref "IC4") (pin "9") (pinfunction "RA7_9") (pintype "bidirectional"))
      (node (ref "Q1") (pin "1") (pinfunction "X1_1") (pintype "bidirectional"))
    )
    (net (code "47") (name "Net-(IC4-RB4)") (class "Default")
      (node (ref "IC4") (pin "25") (pinfunction "RB4_25") (pintype "bidirectional"))
      (node (ref "R10") (pin "2") (pinfunction "2_2") (pintype "passive"))
    )
    (net (code "48") (name "Net-(IC4-RB5)") (class "Default")
      (node (ref "IC4") (pin "26") (pinfunction "RB5_26") (pintype "bidirectional"))
      (node (ref "IC5") (pin "2") (pinfunction "~{RE}_2") (pintype "input"))
      (node (ref "IC5") (pin "3") (pinfunction "DE_3") (pintype "input"))
    )
    (net (code "49") (name "Net-(IC4-RC2)") (class "Default")
      (node (ref "IC4") (pin "13") (pinfunction "RC2_13") (pintype "bidirectional"))
      (node (ref "R2") (pin "1") (pinfunction "1_1") (pintype "passive"))
    )
    (net (code "50") (name "Net-(IC4-RC6)") (class "Default")
      (node (ref "IC4") (pin "17") (pinfunction "RC6_17") (pintype "bidirectional"))
      (node (ref "IC5") (pin "4") (pinfunction "DI_4") (pintype "input"))
    )
    (net (code "51") (name "Net-(IC4-RC7)") (class "Default")
      (node (ref "IC4") (pin "18") (pinfunction "RC7_18") (pintype "bidirectional"))
      (node (ref "IC5") (pin "1") (pinfunction "RO_1") (pintype "output"))
    )
    (net (code "52") (name "Net-(IC7-CAP+)") (class "Default")
      (node (ref "C9") (pin "1") (pinfunction "1_1") (pintype "passive"))
      (node (ref "IC7") (pin "2") (pinfunction "CAP+_2") (pintype "passive"))
    )
    (net (code "53") (name "Net-(IC7-CAP-)") (class "Default")
      (node (ref "C9") (pin "2") (pinfunction "2_2") (pintype "passive"))
      (node (ref "IC7") (pin "4") (pinfunction "CAP-_4") (pintype "passive"))
    )
    (net (code "54") (name "Net-(K1-A)") (class "Default")
      (node (ref "K1") (pin "2") (pinfunction "A_2") (pintype "passive"))
      (node (ref "R10") (pin "1") (pinfunction "1_1") (pintype "passive"))
    )
    (net (code "55") (name "Net-(K1-DS3)") (class "Default")
      (node (ref "F1") (pin "1") (pinfunction "1_1") (pintype "passive"))
      (node (ref "K1") (pin "6") (pinfunction "DS3_6") (pintype "passive"))
      (node (ref "U$2") (pin "1") (pinfunction "AC(L)_1") (pintype "input"))
    )
    (net (code "56") (name "Net-(R14-Pad1)") (class "Default")
      (node (ref "R14") (pin "1") (pinfunction "1_1") (pintype "passive"))
      (node (ref "R19") (pin "1") (pinfunction "1_1") (pintype "passive"))
      (node (ref "R20") (pin "2") (pinfunction "2_2") (pintype "passive"))
      (node (ref "R21") (pin "2") (pinfunction "2_2") (pintype "passive"))
    )
    (net (code "57") (name "unconnected-(CON2E-SK-PadP$5)") (class "Default")
      (node (ref "CON2") (pin "P$5") (pinfunction "SK_P$5") (pintype "passive"))
    )
    (net (code "58") (name "unconnected-(CON3-P$1-Pad1)") (class "Default")
      (node (ref "CON3") (pin "1") (pinfunction "P$1_1") (pintype "bidirectional"))
    )
    (net (code "59") (name "unconnected-(CON3-P$9-Pad9)") (class "Default")
      (node (ref "CON3") (pin "9") (pinfunction "P$9_9") (pintype "bidirectional"))
    )
    (net (code "60") (name "unconnected-(FTDI-Pad1)") (class "Default")
      (node (ref "FTDI") (pin "1") (pinfunction "1_1") (pintype "passive"))
    )
    (net (code "61") (name "unconnected-(FTDI-Pad4)") (class "Default")
      (node (ref "FTDI") (pin "4") (pinfunction "4_4") (pintype "passive"))
    )
    (net (code "62") (name "unconnected-(IC6-NC-Pad8)") (class "Default")
      (node (ref "IC6") (pin "8") (pinfunction "NC_8") (pintype "no_connect"))
    )
    (net (code "63") (name "unconnected-(IC6-NC_2-Pad1)") (class "Default")
      (node (ref "IC6") (pin "1") (pinfunction "NC_2_1") (pintype "no_connect"))
    )
    (net (code "64") (name "unconnected-(IC7-LV-Pad6)") (class "Default")
      (node (ref "IC7") (pin "6") (pinfunction "LV_6") (pintype "passive"))
    )
    (net (code "65") (name "unconnected-(IC7-OSC-Pad7)") (class "Default")
      (node (ref "IC7") (pin "7") (pinfunction "OSC_7") (pintype "input"))
    )
    (net (code "66") (name "unconnected-(ICD-Pad6)") (class "Default")
      (node (ref "ICD") (pin "6") (pinfunction "6_6") (pintype "passive"))
    )
    (net (code "67") (name "unconnected-(K1-DS2-Pad5)") (class "Default")
      (node (ref "K1") (pin "5") (pinfunction "DS2_5") (pintype "passive"))
    )
    (net (code "68") (name "unconnected-(P1-Pad3)") (class "Default")
      (node (ref "P1") (pin "3") (pinfunction "3_3") (pintype "passive"))
    )
  )
)
